# ALLPRINT-CAPBOARD-677512-ENCODER-INPUT.net
KiCad netlist of a schematic drawn in Altium Designer
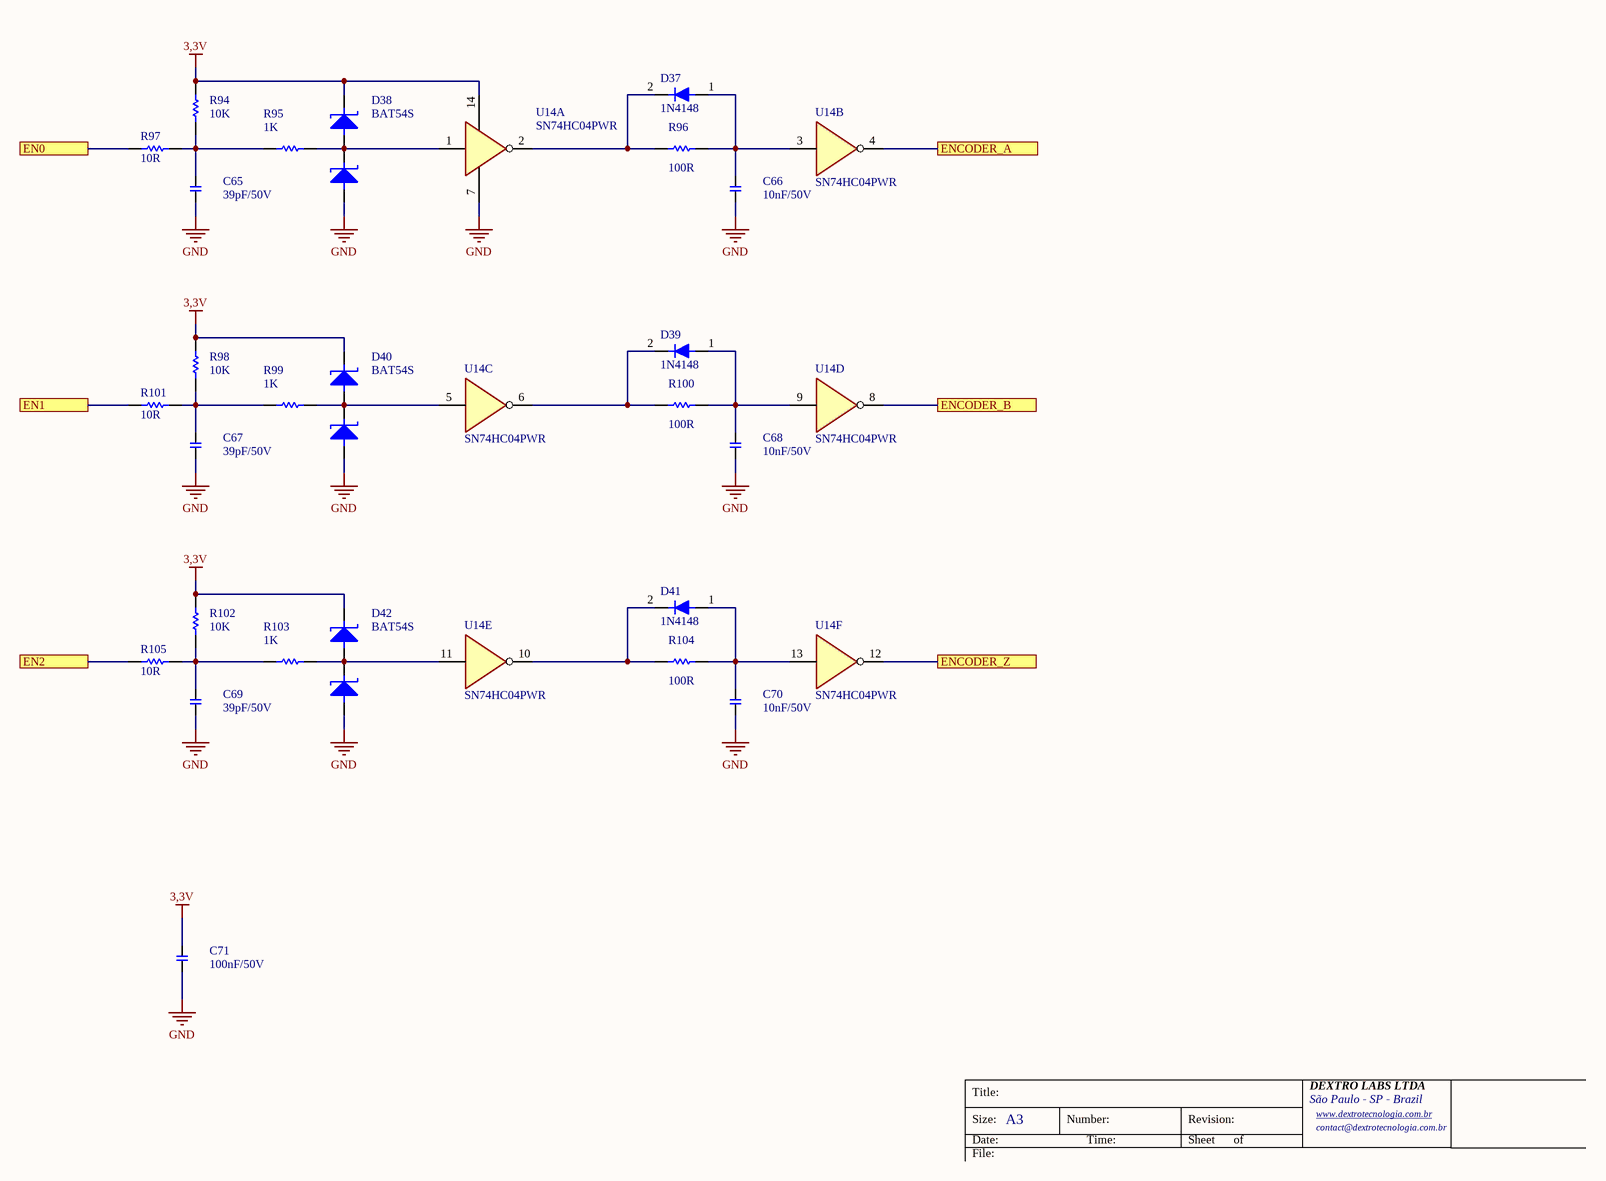
[diagram p0: ALLPRINT-CAPBOARD-677512-ENCODER-INPUT.SchDoc]

(export (version "E")
  (design (tool "Eeschema 10.0.6"))
  (components
    (comp (ref "C65")
      (value "39pF/50V")
      (footprint "CAP-0603")
      (description "50V 39pF X7R ±10% 0603 Multilayer Ceramic Capacitors MLCC - SMD/SMT ROHS")
      (libsource (lib "dextro-labs") (part "CAP-39pF/50V-0603-X7R-MLCC"))
    )
    (comp (ref "C66")
      (value "10nF/50V")
      (footprint "CAP-0603")
      (description "50V 10nF X7R ±10% 0603 Multilayer Ceramic Capacitors MLCC - SMD/SMT ROHS")
      (libsource (lib "dextro-labs") (part "CAP-10nF/50V-0603-X7R-MLCC"))
    )
    (comp (ref "C67")
      (value "39pF/50V")
      (footprint "CAP-0603")
      (description "50V 39pF X7R ±10% 0603 Multilayer Ceramic Capacitors MLCC - SMD/SMT ROHS")
      (libsource (lib "dextro-labs") (part "CAP-39pF/50V-0603-X7R-MLCC"))
    )
    (comp (ref "C68")
      (value "10nF/50V")
      (footprint "CAP-0603")
      (description "50V 10nF X7R ±10% 0603 Multilayer Ceramic Capacitors MLCC - SMD/SMT ROHS")
      (libsource (lib "dextro-labs") (part "CAP-10nF/50V-0603-X7R-MLCC"))
    )
    (comp (ref "C69")
      (value "39pF/50V")
      (footprint "CAP-0603")
      (description "50V 39pF X7R ±10% 0603 Multilayer Ceramic Capacitors MLCC - SMD/SMT ROHS")
      (libsource (lib "dextro-labs") (part "CAP-39pF/50V-0603-X7R-MLCC"))
    )
    (comp (ref "C70")
      (value "10nF/50V")
      (footprint "CAP-0603")
      (description "50V 10nF X7R ±10% 0603 Multilayer Ceramic Capacitors MLCC - SMD/SMT ROHS")
      (libsource (lib "dextro-labs") (part "CAP-10nF/50V-0603-X7R-MLCC"))
    )
    (comp (ref "C71")
      (value "100nF/50V")
      (footprint "CAP-0603")
      (description "50V 100nF X7R ±10% 0603 Multilayer Ceramic Capacitors MLCC - SMD/SMT ROHS")
      (libsource (lib "dextro-labs") (part "CAP-100nF/50V-0603-X7R-MLCC"))
    )
    (comp (ref "D37")
      (value "1N4148")
      (footprint "SOD123")
      (description "1A 4ns 75V Independent 1V@50mA 150mA SOD-123 Single Diodes RoHS")
      (libsource (lib "dextro-labs") (part "1N4148"))
    )
    (comp (ref "D38")
      (value "BAT54S")
      (footprint "SOT23-3")
      (description "30V Dual 200mA 800mV@100mA SOT-23 Schottky Barrier Diodes (SBD) ROHS")
      (libsource (lib "dextro-labs") (part "BAT54S"))
    )
    (comp (ref "D39")
      (value "1N4148")
      (footprint "SOD123")
      (description "1A 4ns 75V Independent 1V@50mA 150mA SOD-123 Single Diodes RoHS")
      (libsource (lib "dextro-labs") (part "1N4148"))
    )
    (comp (ref "D40")
      (value "BAT54S")
      (footprint "SOT23-3")
      (description "30V Dual 200mA 800mV@100mA SOT-23 Schottky Barrier Diodes (SBD) ROHS")
      (libsource (lib "dextro-labs") (part "BAT54S"))
    )
    (comp (ref "D41")
      (value "1N4148")
      (footprint "SOD123")
      (description "1A 4ns 75V Independent 1V@50mA 150mA SOD-123 Single Diodes RoHS")
      (libsource (lib "dextro-labs") (part "1N4148"))
    )
    (comp (ref "D42")
      (value "BAT54S")
      (footprint "SOT23-3")
      (description "30V Dual 200mA 800mV@100mA SOT-23 Schottky Barrier Diodes (SBD) ROHS")
      (libsource (lib "dextro-labs") (part "BAT54S"))
    )
    (comp (ref "R94")
      (value "10K")
      (footprint "RES-0805")
      (description "100mW Thick Film Resistor 75V ±100ppm/℃ ±1% 10K Chip Resistor - Surface Mount ROHS")
      (libsource (lib "dextro-labs") (part "RES-10K-1%-125mW-0805"))
    )
    (comp (ref "R95")
      (value "1K")
      (footprint "RES-0603")
      (description "100mW Thick Film Resistor 75V ±100ppm/℃ ±1% 1kΩ 0603 Chip Resistor - Surface Mount ROHS")
      (libsource (lib "dextro-labs") (part "RES-1K-1%-100mW-0603"))
    )
    (comp (ref "R96")
      (value "100R")
      (footprint "RES-0603")
      (description "100mW Thick Film Resistor 75V ±100ppm/℃ ±1% 100Ω 0603 Chip Resistor - Surface Mount ROHS")
      (libsource (lib "dextro-labs") (part "RES-100R-1%-100mW-0603"))
    )
    (comp (ref "R97")
      (value "10R")
      (footprint "RES-0603")
      (description "100mW Thick Film Resistor 75V ±1% ±400ppm/℃ 10Ω 0603 Chip Resistor - Surface Mount ROHS")
      (libsource (lib "dextro-labs") (part "RES-10R-1%-100mW-0603"))
    )
    (comp (ref "R98")
      (value "10K")
      (footprint "RES-0805")
      (description "100mW Thick Film Resistor 75V ±100ppm/℃ ±1% 10K Chip Resistor - Surface Mount ROHS")
      (libsource (lib "dextro-labs") (part "RES-10K-1%-125mW-0805"))
    )
    (comp (ref "R99")
      (value "1K")
      (footprint "RES-0603")
      (description "100mW Thick Film Resistor 75V ±100ppm/℃ ±1% 1kΩ 0603 Chip Resistor - Surface Mount ROHS")
      (libsource (lib "dextro-labs") (part "RES-1K-1%-100mW-0603"))
    )
    (comp (ref "R100")
      (value "100R")
      (footprint "RES-0603")
      (description "100mW Thick Film Resistor 75V ±100ppm/℃ ±1% 100Ω 0603 Chip Resistor - Surface Mount ROHS")
      (libsource (lib "dextro-labs") (part "RES-100R-1%-100mW-0603"))
    )
    (comp (ref "R101")
      (value "10R")
      (footprint "RES-0603")
      (description "100mW Thick Film Resistor 75V ±1% ±400ppm/℃ 10Ω 0603 Chip Resistor - Surface Mount ROHS")
      (libsource (lib "dextro-labs") (part "RES-10R-1%-100mW-0603"))
    )
    (comp (ref "R102")
      (value "10K")
      (footprint "RES-0805")
      (description "100mW Thick Film Resistor 75V ±100ppm/℃ ±1% 10K Chip Resistor - Surface Mount ROHS")
      (libsource (lib "dextro-labs") (part "RES-10K-1%-125mW-0805"))
    )
    (comp (ref "R103")
      (value "1K")
      (footprint "RES-0603")
      (description "100mW Thick Film Resistor 75V ±100ppm/℃ ±1% 1kΩ 0603 Chip Resistor - Surface Mount ROHS")
      (libsource (lib "dextro-labs") (part "RES-1K-1%-100mW-0603"))
    )
    (comp (ref "R104")
      (value "100R")
      (footprint "RES-0603")
      (description "100mW Thick Film Resistor 75V ±100ppm/℃ ±1% 100Ω 0603 Chip Resistor - Surface Mount ROHS")
      (libsource (lib "dextro-labs") (part "RES-100R-1%-100mW-0603"))
    )
    (comp (ref "R105")
      (value "10R")
      (footprint "RES-0603")
      (description "100mW Thick Film Resistor 75V ±1% ±400ppm/℃ 10Ω 0603 Chip Resistor - Surface Mount ROHS")
      (libsource (lib "dextro-labs") (part "RES-10R-1%-100mW-0603"))
    )
    (comp (ref "U14")
      (value "SN74HC04PWR")
      (footprint "TSSOP-14")
      (description "2V~6V 16ns@6V,50pF 2uA 6 1 TSSOP-14 Gates and Inverters RoHS")
      (libsource (lib "dextro-labs") (part "SN74HC04PWR"))
    )
  )
  (nets
    (net (code "1") (name "/EN0") (class "Default")
      (node (ref "R97") (pin "1") (pinfunction "1_1") (pintype "passive"))
    )
    (net (code "2") (name "/EN1") (class "Default")
      (node (ref "R101") (pin "1") (pinfunction "1_1") (pintype "passive"))
    )
    (net (code "3") (name "/EN2") (class "Default")
      (node (ref "R105") (pin "1") (pinfunction "1_1") (pintype "passive"))
    )
    (net (code "4") (name "/ENCODER_A") (class "Default")
      (node (ref "U14") (pin "4") (pinfunction "4Y_4") (pintype "passive"))
    )
    (net (code "5") (name "/ENCODER_B") (class "Default")
      (node (ref "U14") (pin "8") (pinfunction "8_8") (pintype "passive"))
    )
    (net (code "6") (name "/ENCODER_Z") (class "Default")
      (node (ref "U14") (pin "12") (pinfunction "12_12") (pintype "passive"))
    )
    (net (code "7") (name "3,3V") (class "Default")
      (node (ref "C71") (pin "2") (pinfunction "2_2") (pintype "passive"))
      (node (ref "D38") (pin "2") (pinfunction "2_2") (pintype "passive"))
      (node (ref "D40") (pin "2") (pinfunction "2_2") (pintype "passive"))
      (node (ref "D42") (pin "2") (pinfunction "2_2") (pintype "passive"))
      (node (ref "R102") (pin "2") (pinfunction "2_2") (pintype "passive"))
      (node (ref "R94") (pin "2") (pinfunction "2_2") (pintype "passive"))
      (node (ref "R98") (pin "2") (pinfunction "2_2") (pintype "passive"))
      (node (ref "U14") (pin "14") (pinfunction "VCC_14") (pintype "passive"))
    )
    (net (code "8") (name "GND") (class "Default")
      (node (ref "C65") (pin "1") (pinfunction "1_1") (pintype "passive"))
      (node (ref "C66") (pin "1") (pinfunction "1_1") (pintype "passive"))
      (node (ref "C67") (pin "1") (pinfunction "1_1") (pintype "passive"))
      (node (ref "C68") (pin "1") (pinfunction "1_1") (pintype "passive"))
      (node (ref "C69") (pin "1") (pinfunction "1_1") (pintype "passive"))
      (node (ref "C70") (pin "1") (pinfunction "1_1") (pintype "passive"))
      (node (ref "C71") (pin "1") (pinfunction "1_1") (pintype "passive"))
      (node (ref "D38") (pin "1") (pinfunction "1_1") (pintype "passive"))
      (node (ref "D40") (pin "1") (pinfunction "1_1") (pintype "passive"))
      (node (ref "D42") (pin "1") (pinfunction "1_1") (pintype "passive"))
      (node (ref "U14") (pin "7") (pinfunction "GND_7") (pintype "passive"))
    )
    (net (code "9") (name "Net-(C65-Pad2)") (class "Default")
      (node (ref "C65") (pin "2") (pinfunction "2_2") (pintype "passive"))
      (node (ref "R94") (pin "1") (pinfunction "1_1") (pintype "passive"))
      (node (ref "R95") (pin "1") (pinfunction "1_1") (pintype "passive"))
      (node (ref "R97") (pin "2") (pinfunction "2_2") (pintype "passive"))
    )
    (net (code "10") (name "Net-(C67-Pad2)") (class "Default")
      (node (ref "C67") (pin "2") (pinfunction "2_2") (pintype "passive"))
      (node (ref "R101") (pin "2") (pinfunction "2_2") (pintype "passive"))
      (node (ref "R98") (pin "1") (pinfunction "1_1") (pintype "passive"))
      (node (ref "R99") (pin "1") (pinfunction "1_1") (pintype "passive"))
    )
    (net (code "11") (name "Net-(C69-Pad2)") (class "Default")
      (node (ref "C69") (pin "2") (pinfunction "2_2") (pintype "passive"))
      (node (ref "R102") (pin "1") (pinfunction "1_1") (pintype "passive"))
      (node (ref "R103") (pin "1") (pinfunction "1_1") (pintype "passive"))
      (node (ref "R105") (pin "2") (pinfunction "2_2") (pintype "passive"))
    )
    (net (code "12") (name "Net-(D37-A1)") (class "Default")
      (node (ref "C66") (pin "2") (pinfunction "2_2") (pintype "passive"))
      (node (ref "D37") (pin "1") (pinfunction "A1_1") (pintype "passive"))
      (node (ref "R96") (pin "2") (pinfunction "2_2") (pintype "passive"))
      (node (ref "U14") (pin "3") (pinfunction "4A_3") (pintype "passive"))
    )
    (net (code "13") (name "Net-(D37-K)") (class "Default")
      (node (ref "D37") (pin "2") (pinfunction "K_2") (pintype "passive"))
      (node (ref "R96") (pin "1") (pinfunction "1_1") (pintype "passive"))
      (node (ref "U14") (pin "2") (pinfunction "2_2") (pintype "passive"))
    )
    (net (code "14") (name "Net-(D39-A1)") (class "Default")
      (node (ref "C68") (pin "2") (pinfunction "2_2") (pintype "passive"))
      (node (ref "D39") (pin "1") (pinfunction "A1_1") (pintype "passive"))
      (node (ref "R100") (pin "2") (pinfunction "2_2") (pintype "passive"))
      (node (ref "U14") (pin "9") (pinfunction "9_9") (pintype "passive"))
    )
    (net (code "15") (name "Net-(D39-K)") (class "Default")
      (node (ref "D39") (pin "2") (pinfunction "K_2") (pintype "passive"))
      (node (ref "R100") (pin "1") (pinfunction "1_1") (pintype "passive"))
      (node (ref "U14") (pin "6") (pinfunction "6_6") (pintype "passive"))
    )
    (net (code "16") (name "Net-(D40-Pad3)") (class "Default")
      (node (ref "D40") (pin "3") (pinfunction "3_3") (pintype "passive"))
      (node (ref "R99") (pin "2") (pinfunction "2_2") (pintype "passive"))
      (node (ref "U14") (pin "5") (pinfunction "5_5") (pintype "passive"))
    )
    (net (code "17") (name "Net-(D41-A1)") (class "Default")
      (node (ref "C70") (pin "2") (pinfunction "2_2") (pintype "passive"))
      (node (ref "D41") (pin "1") (pinfunction "A1_1") (pintype "passive"))
      (node (ref "R104") (pin "2") (pinfunction "2_2") (pintype "passive"))
      (node (ref "U14") (pin "13") (pinfunction "13_13") (pintype "passive"))
    )
    (net (code "18") (name "Net-(D41-K)") (class "Default")
      (node (ref "D41") (pin "2") (pinfunction "K_2") (pintype "passive"))
      (node (ref "R104") (pin "1") (pinfunction "1_1") (pintype "passive"))
      (node (ref "U14") (pin "10") (pinfunction "10_10") (pintype "passive"))
    )
    (net (code "19") (name "Net-(D42-Pad3)") (class "Default")
      (node (ref "D42") (pin "3") (pinfunction "3_3") (pintype "passive"))
      (node (ref "R103") (pin "2") (pinfunction "2_2") (pintype "passive"))
      (node (ref "U14") (pin "11") (pinfunction "11_11") (pintype "passive"))
    )
    (net (code "20") (name "Net-(U14A-1A)") (class "Default")
      (node (ref "D38") (pin "3") (pinfunction "3_3") (pintype "passive"))
      (node (ref "R95") (pin "2") (pinfunction "2_2") (pintype "passive"))
      (node (ref "U14") (pin "1") (pinfunction "1A_1") (pintype "passive"))
    )
  )
)
